# uino-1284p.net
KiCad netlist of a schematic drawn in EAGLE
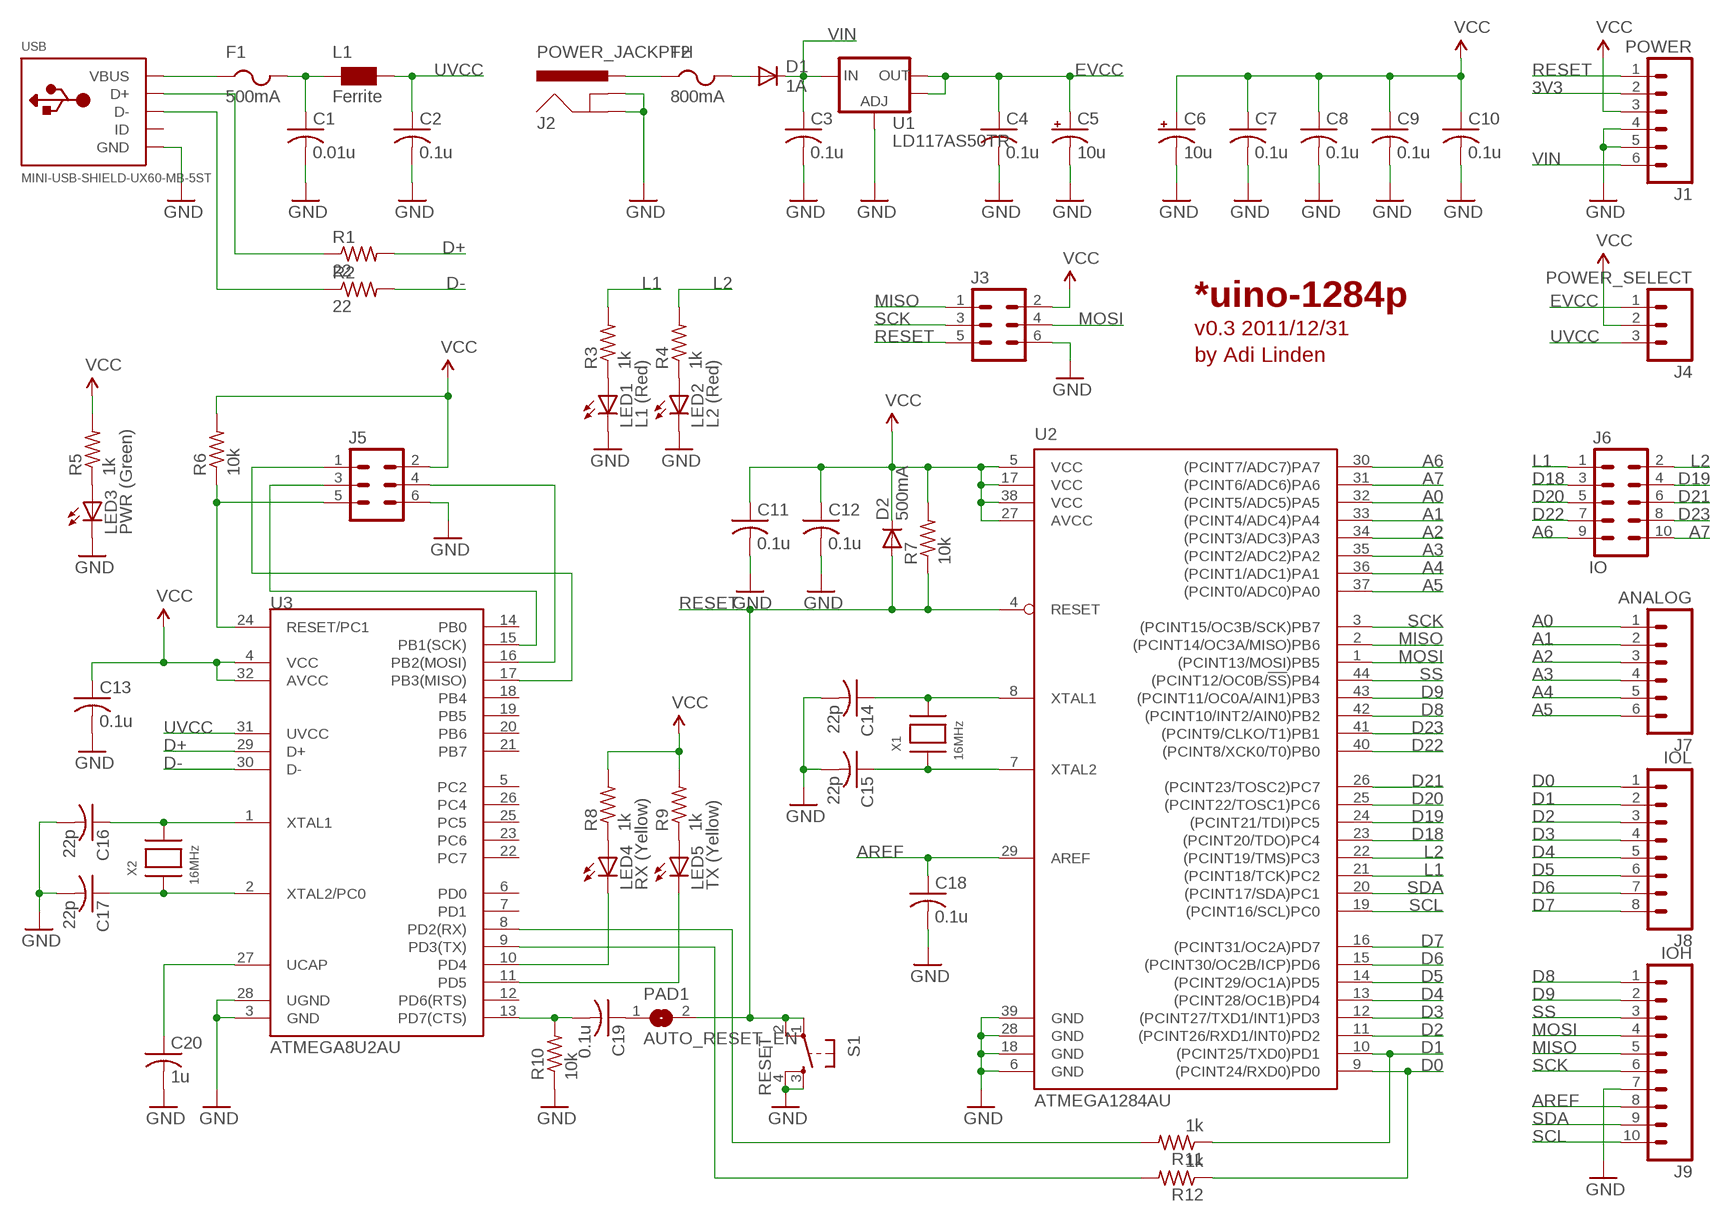
[diagram p0: schematic, sheet 1]

(export (version "E")
  (design (tool "Eeschema 10.0.6"))
  (components
    (comp (ref "C1")
      (value "0.01u")
      (footprint "eagle-import:C0805")
      (libsource (lib "eagle-import") (part "C-USC0805"))
    )
    (comp (ref "C2")
      (value "0.1u")
      (footprint "eagle-import:C0805")
      (libsource (lib "eagle-import") (part "C-USC0805"))
    )
    (comp (ref "C3")
      (value "0.1u")
      (footprint "eagle-import:C0805")
      (libsource (lib "eagle-import") (part "C-USC0805"))
    )
    (comp (ref "C4")
      (value "0.1u")
      (footprint "eagle-import:C0805")
      (libsource (lib "eagle-import") (part "C-USC0805"))
    )
    (comp (ref "C5")
      (value "10u")
      (footprint "eagle-import:CT3216")
      (libsource (lib "eagle-import") (part "CPOL-USCT3216"))
    )
    (comp (ref "C6")
      (value "10u")
      (footprint "eagle-import:CT3216")
      (libsource (lib "eagle-import") (part "CPOL-USCT3216"))
    )
    (comp (ref "C7")
      (value "0.1u")
      (footprint "eagle-import:C0805")
      (libsource (lib "eagle-import") (part "C-USC0805"))
    )
    (comp (ref "C8")
      (value "0.1u")
      (footprint "eagle-import:C0805")
      (libsource (lib "eagle-import") (part "C-USC0805"))
    )
    (comp (ref "C9")
      (value "0.1u")
      (footprint "eagle-import:C0805")
      (libsource (lib "eagle-import") (part "C-USC0805"))
    )
    (comp (ref "C10")
      (value "0.1u")
      (footprint "eagle-import:C0805")
      (libsource (lib "eagle-import") (part "C-USC0805"))
    )
    (comp (ref "C11")
      (value "0.1u")
      (footprint "eagle-import:C0805")
      (libsource (lib "eagle-import") (part "C-USC0805"))
    )
    (comp (ref "C12")
      (value "0.1u")
      (footprint "eagle-import:C0805")
      (libsource (lib "eagle-import") (part "C-USC0805"))
    )
    (comp (ref "C13")
      (value "0.1u")
      (footprint "eagle-import:C0805")
      (libsource (lib "eagle-import") (part "C-USC0805"))
    )
    (comp (ref "C14")
      (value "22p")
      (footprint "eagle-import:C0805")
      (libsource (lib "eagle-import") (part "C-USC0805"))
    )
    (comp (ref "C15")
      (value "22p")
      (footprint "eagle-import:C0805")
      (libsource (lib "eagle-import") (part "C-USC0805"))
    )
    (comp (ref "C16")
      (value "22p")
      (footprint "eagle-import:C0805")
      (libsource (lib "eagle-import") (part "C-USC0805"))
    )
    (comp (ref "C17")
      (value "22p")
      (footprint "eagle-import:C0805")
      (libsource (lib "eagle-import") (part "C-USC0805"))
    )
    (comp (ref "C18")
      (value "0.1u")
      (footprint "eagle-import:C0805")
      (libsource (lib "eagle-import") (part "C-USC0805"))
    )
    (comp (ref "C19")
      (value "0.1u")
      (footprint "eagle-import:C0805")
      (libsource (lib "eagle-import") (part "C-USC0805"))
    )
    (comp (ref "C20")
      (value "1u")
      (footprint "eagle-import:C0805")
      (libsource (lib "eagle-import") (part "C-USC0805"))
    )
    (comp (ref "D1")
      (value "1A")
      (footprint "eagle-import:SOD123")
      (libsource (lib "eagle-import") (part "MBR0520LT"))
    )
    (comp (ref "D2")
      (value "500mA")
      (footprint "eagle-import:SOD123")
      (libsource (lib "eagle-import") (part "MBR0520LT"))
    )
    (comp (ref "F1")
      (value "500mA")
      (footprint "eagle-import:R0805")
      (libsource (lib "eagle-import") (part "PTCFUSE-0805"))
    )
    (comp (ref "F2")
      (value "800mA")
      (footprint "eagle-import:R0805")
      (libsource (lib "eagle-import") (part "PTCFUSE-0805"))
    )
    (comp (ref "J1")
      (value "POWER")
      (footprint "eagle-import:1X06")
      (libsource (lib "eagle-import") (part "M06SIP"))
    )
    (comp (ref "J2")
      (value "POWER_JACKPTH")
      (footprint "eagle-import:POWER_JACK_PTH")
      (libsource (lib "eagle-import") (part "POWER_JACKPTH"))
    )
    (comp (ref "J3")
      (value "M03X2")
      (footprint "eagle-import:2X03")
      (libsource (lib "eagle-import") (part "M03X2"))
    )
    (comp (ref "J4")
      (value "POWER_SELECT")
      (footprint "eagle-import:1X03")
      (libsource (lib "eagle-import") (part "M03PTH"))
    )
    (comp (ref "J5")
      (value "M03X2")
      (footprint "eagle-import:2X03")
      (libsource (lib "eagle-import") (part "M03X2"))
    )
    (comp (ref "J6")
      (value "IO")
      (footprint "eagle-import:2X05")
      (libsource (lib "eagle-import") (part "M05X2"))
    )
    (comp (ref "J7")
      (value "ANALOG")
      (footprint "eagle-import:1X06")
      (libsource (lib "eagle-import") (part "M06SIP"))
    )
    (comp (ref "J8")
      (value "IOL")
      (footprint "eagle-import:1X08")
      (libsource (lib "eagle-import") (part "M081X08"))
    )
    (comp (ref "J9")
      (value "IOH")
      (footprint "eagle-import:1X10")
      (libsource (lib "eagle-import") (part "M101X10"))
    )
    (comp (ref "L1")
      (value "Ferrite")
      (footprint "eagle-import:0805")
      (libsource (lib "eagle-import") (part "WE-CBF_0805"))
    )
    (comp (ref "LED1")
      (value "L1 (Red)")
      (footprint "eagle-import:CHIP-LED0805")
      (libsource (lib "eagle-import") (part "LEDCHIP-LED0805"))
    )
    (comp (ref "LED2")
      (value "L2 (Red)")
      (footprint "eagle-import:CHIP-LED0805")
      (libsource (lib "eagle-import") (part "LEDCHIP-LED0805"))
    )
    (comp (ref "LED3")
      (value "PWR (Green)")
      (footprint "eagle-import:CHIP-LED0805")
      (libsource (lib "eagle-import") (part "LEDCHIP-LED0805"))
    )
    (comp (ref "LED4")
      (value "RX (Yellow)")
      (footprint "eagle-import:CHIP-LED0805")
      (libsource (lib "eagle-import") (part "LEDCHIP-LED0805"))
    )
    (comp (ref "LED5")
      (value "TX (Yellow)")
      (footprint "eagle-import:CHIP-LED0805")
      (libsource (lib "eagle-import") (part "LEDCHIP-LED0805"))
    )
    (comp (ref "PAD1")
      (value "AUTO_RESET_EN")
      (footprint "eagle-import:SJ")
      (libsource (lib "eagle-import") (part "SJ"))
    )
    (comp (ref "R1")
      (value "22")
      (footprint "eagle-import:R0805")
      (libsource (lib "eagle-import") (part "R-US_R0805"))
    )
    (comp (ref "R2")
      (value "22")
      (footprint "eagle-import:R0805")
      (libsource (lib "eagle-import") (part "R-US_R0805"))
    )
    (comp (ref "R3")
      (value "1k")
      (footprint "eagle-import:R0805")
      (libsource (lib "eagle-import") (part "R-US_R0805"))
    )
    (comp (ref "R4")
      (value "1k")
      (footprint "eagle-import:R0805")
      (libsource (lib "eagle-import") (part "R-US_R0805"))
    )
    (comp (ref "R5")
      (value "1k")
      (footprint "eagle-import:R0805")
      (libsource (lib "eagle-import") (part "R-US_R0805"))
    )
    (comp (ref "R6")
      (value "10k")
      (footprint "eagle-import:R0805")
      (libsource (lib "eagle-import") (part "R-US_R0805"))
    )
    (comp (ref "R7")
      (value "10k")
      (footprint "eagle-import:R0805")
      (libsource (lib "eagle-import") (part "R-US_R0805"))
    )
    (comp (ref "R8")
      (value "1k")
      (footprint "eagle-import:R0805")
      (libsource (lib "eagle-import") (part "R-US_R0805"))
    )
    (comp (ref "R9")
      (value "1k")
      (footprint "eagle-import:R0805")
      (libsource (lib "eagle-import") (part "R-US_R0805"))
    )
    (comp (ref "R10")
      (value "10k")
      (footprint "eagle-import:R0805")
      (libsource (lib "eagle-import") (part "R-US_R0805"))
    )
    (comp (ref "R11")
      (value "1k")
      (footprint "eagle-import:R0805")
      (libsource (lib "eagle-import") (part "R-US_R0805"))
    )
    (comp (ref "R12")
      (value "1k")
      (footprint "eagle-import:R0805")
      (libsource (lib "eagle-import") (part "R-US_R0805"))
    )
    (comp (ref "S1")
      (value "RESET")
      (footprint "eagle-import:TACTILE_SWITCH_SMD")
      (libsource (lib "eagle-import") (part "TAC_SWITCHSMD"))
    )
    (comp (ref "U1")
      (value "LD117AS50TR")
      (footprint "eagle-import:SOT223")
      (libsource (lib "eagle-import") (part "V_REG_LM1117SOT223"))
    )
    (comp (ref "U2")
      (value "ATMEGA1284AU")
      (footprint "eagle-import:TQFP44")
      (fields (field (name "MPN") "ATMEGA644PV-10AU"))
      (libsource (lib "eagle-import") (part "ATMEGA1284P-AU"))
    )
    (comp (ref "U3")
      (value "ATMEGA8U2AU")
      (footprint "eagle-import:TQFP32-08")
      (libsource (lib "eagle-import") (part "ATMEGA8U2AU"))
    )
    (comp (ref "USB")
      (value "MINI-USB-SHIELD-UX60-MB-5ST")
      (footprint "eagle-import:USB-MINIB")
      (libsource (lib "eagle-import") (part "USBMINIB"))
    )
    (comp (ref "X1")
      (value "16MHz")
      (footprint "eagle-import:NX5032")
      (libsource (lib "eagle-import") (part "XTALNX5032"))
    )
    (comp (ref "X2")
      (value "16MHz")
      (footprint "eagle-import:NX5032")
      (libsource (lib "eagle-import") (part "XTALNX5032"))
    )
  )
  (nets
    (net (code "1") (name "/3V3") (class "Default")
      (node (ref "J1") (pin "2") (pinfunction "2_2") (pintype "passive"))
    )
    (net (code "2") (name "/A0") (class "Default")
      (node (ref "J7") (pin "1") (pinfunction "1_1") (pintype "passive"))
      (node (ref "U2") (pin "32") (pinfunction "(PCINT5/ADC5)PA5_32") (pintype "bidirectional"))
    )
    (net (code "3") (name "/A1") (class "Default")
      (node (ref "J7") (pin "2") (pinfunction "2_2") (pintype "passive"))
      (node (ref "U2") (pin "33") (pinfunction "(PCINT4/ADC4)PA4_33") (pintype "bidirectional"))
    )
    (net (code "4") (name "/A2") (class "Default")
      (node (ref "J7") (pin "3") (pinfunction "3_3") (pintype "passive"))
      (node (ref "U2") (pin "34") (pinfunction "(PCINT3/ADC3)PA3_34") (pintype "bidirectional"))
    )
    (net (code "5") (name "/A3") (class "Default")
      (node (ref "J7") (pin "4") (pinfunction "4_4") (pintype "passive"))
      (node (ref "U2") (pin "35") (pinfunction "(PCINT2/ADC2)PA2_35") (pintype "bidirectional"))
    )
    (net (code "6") (name "/A4") (class "Default")
      (node (ref "J7") (pin "5") (pinfunction "5_5") (pintype "passive"))
      (node (ref "U2") (pin "36") (pinfunction "(PCINT1/ADC1)PA1_36") (pintype "bidirectional"))
    )
    (net (code "7") (name "/A5") (class "Default")
      (node (ref "J7") (pin "6") (pinfunction "6_6") (pintype "passive"))
      (node (ref "U2") (pin "37") (pinfunction "(PCINT0/ADC0)PA0_37") (pintype "bidirectional"))
    )
    (net (code "8") (name "/A6") (class "Default")
      (node (ref "J6") (pin "9") (pinfunction "9_9") (pintype "passive"))
      (node (ref "U2") (pin "30") (pinfunction "(PCINT7/ADC7)PA7_30") (pintype "bidirectional"))
    )
    (net (code "9") (name "/A7") (class "Default")
      (node (ref "J6") (pin "10") (pinfunction "10_10") (pintype "passive"))
      (node (ref "U2") (pin "31") (pinfunction "(PCINT6/ADC6)PA6_31") (pintype "bidirectional"))
    )
    (net (code "10") (name "/AREF") (class "Default")
      (node (ref "C18") (pin "1") (pinfunction "1_1") (pintype "passive"))
      (node (ref "J9") (pin "8") (pinfunction "8_8") (pintype "passive"))
      (node (ref "U2") (pin "29") (pinfunction "AREF_29") (pintype "passive"))
    )
    (net (code "11") (name "/D+") (class "Default")
      (node (ref "R1") (pin "2") (pinfunction "2_2") (pintype "passive"))
      (node (ref "U3") (pin "29") (pinfunction "D+_29") (pintype "bidirectional"))
    )
    (net (code "12") (name "/D-") (class "Default")
      (node (ref "R2") (pin "2") (pinfunction "2_2") (pintype "passive"))
      (node (ref "U3") (pin "30") (pinfunction "D-_30") (pintype "bidirectional"))
    )
    (net (code "13") (name "/D0") (class "Default")
      (node (ref "J8") (pin "1") (pinfunction "1_1") (pintype "passive"))
      (node (ref "R12") (pin "1") (pinfunction "1_1") (pintype "passive"))
      (node (ref "U2") (pin "9") (pinfunction "(PCINT24/RXD0)PD0_9") (pintype "bidirectional"))
    )
    (net (code "14") (name "/D1") (class "Default")
      (node (ref "J8") (pin "2") (pinfunction "2_2") (pintype "passive"))
      (node (ref "R11") (pin "1") (pinfunction "1_1") (pintype "passive"))
      (node (ref "U2") (pin "10") (pinfunction "(PCINT25/TXD0)PD1_10") (pintype "bidirectional"))
    )
    (net (code "15") (name "/D2") (class "Default")
      (node (ref "J8") (pin "3") (pinfunction "3_3") (pintype "passive"))
      (node (ref "U2") (pin "11") (pinfunction "(PCINT26/RXD1/INT0)PD2_11") (pintype "bidirectional"))
    )
    (net (code "16") (name "/D3") (class "Default")
      (node (ref "J8") (pin "4") (pinfunction "4_4") (pintype "passive"))
      (node (ref "U2") (pin "12") (pinfunction "(PCINT27/TXD1/INT1)PD3_12") (pintype "bidirectional"))
    )
    (net (code "17") (name "/D4") (class "Default")
      (node (ref "J8") (pin "5") (pinfunction "5_5") (pintype "passive"))
      (node (ref "U2") (pin "13") (pinfunction "(PCINT28/OC1B)PD4_13") (pintype "bidirectional"))
    )
    (net (code "18") (name "/D5") (class "Default")
      (node (ref "J8") (pin "6") (pinfunction "6_6") (pintype "passive"))
      (node (ref "U2") (pin "14") (pinfunction "(PCINT29/OC1A)PD5_14") (pintype "bidirectional"))
    )
    (net (code "19") (name "/D6") (class "Default")
      (node (ref "J8") (pin "7") (pinfunction "7_7") (pintype "passive"))
      (node (ref "U2") (pin "15") (pinfunction "(PCINT30/OC2B/ICP)PD6_15") (pintype "bidirectional"))
    )
    (net (code "20") (name "/D7") (class "Default")
      (node (ref "J8") (pin "8") (pinfunction "8_8") (pintype "passive"))
      (node (ref "U2") (pin "16") (pinfunction "(PCINT31/OC2A)PD7_16") (pintype "bidirectional"))
    )
    (net (code "21") (name "/D8") (class "Default")
      (node (ref "J9") (pin "1") (pinfunction "1_1") (pintype "passive"))
      (node (ref "U2") (pin "42") (pinfunction "(PCINT10/INT2/AIN0)PB2_42") (pintype "bidirectional"))
    )
    (net (code "22") (name "/D9") (class "Default")
      (node (ref "J9") (pin "2") (pinfunction "2_2") (pintype "passive"))
      (node (ref "U2") (pin "43") (pinfunction "(PCINT11/OC0A/AIN1)PB3_43") (pintype "bidirectional"))
    )
    (net (code "23") (name "/D18") (class "Default")
      (node (ref "J6") (pin "3") (pinfunction "3_3") (pintype "passive"))
      (node (ref "U2") (pin "23") (pinfunction "(PCINT20/TDO)PC4_23") (pintype "output"))
    )
    (net (code "24") (name "/D19") (class "Default")
      (node (ref "J6") (pin "4") (pinfunction "4_4") (pintype "passive"))
      (node (ref "U2") (pin "24") (pinfunction "(PCINT21/TDI)PC5_24") (pintype "output"))
    )
    (net (code "25") (name "/D20") (class "Default")
      (node (ref "J6") (pin "5") (pinfunction "5_5") (pintype "passive"))
      (node (ref "U2") (pin "25") (pinfunction "(PCINT22/TOSC1)PC6_25") (pintype "output"))
    )
    (net (code "26") (name "/D21") (class "Default")
      (node (ref "J6") (pin "6") (pinfunction "6_6") (pintype "passive"))
      (node (ref "U2") (pin "26") (pinfunction "(PCINT23/TOSC2)PC7_26") (pintype "output"))
    )
    (net (code "27") (name "/D22") (class "Default")
      (node (ref "J6") (pin "7") (pinfunction "7_7") (pintype "passive"))
      (node (ref "U2") (pin "40") (pinfunction "(PCINT8/XCK0/T0)PB0_40") (pintype "bidirectional"))
    )
    (net (code "28") (name "/D23") (class "Default")
      (node (ref "J6") (pin "8") (pinfunction "8_8") (pintype "passive"))
      (node (ref "U2") (pin "41") (pinfunction "(PCINT9/CLKO/T1)PB1_41") (pintype "bidirectional"))
    )
    (net (code "29") (name "/EVCC") (class "Default")
      (node (ref "C4") (pin "1") (pinfunction "1_1") (pintype "passive"))
      (node (ref "C5") (pin "+") (pinfunction "+_+") (pintype "passive"))
      (node (ref "J4") (pin "1") (pinfunction "1_1") (pintype "passive"))
      (node (ref "U1") (pin "2") (pinfunction "OUT_2") (pintype "power_in"))
      (node (ref "U1") (pin "4") (pinfunction "OUT_4") (pintype "power_in"))
    )
    (net (code "30") (name "/L1") (class "Default")
      (node (ref "J6") (pin "1") (pinfunction "1_1") (pintype "passive"))
      (node (ref "R3") (pin "2") (pinfunction "2_2") (pintype "passive"))
      (node (ref "U2") (pin "21") (pinfunction "(PCINT18/TCK)PC2_21") (pintype "output"))
    )
    (net (code "31") (name "/L2") (class "Default")
      (node (ref "J6") (pin "2") (pinfunction "2_2") (pintype "passive"))
      (node (ref "R4") (pin "2") (pinfunction "2_2") (pintype "passive"))
      (node (ref "U2") (pin "22") (pinfunction "(PCINT19/TMS)PC3_22") (pintype "output"))
    )
    (net (code "32") (name "/MISO") (class "Default")
      (node (ref "J3") (pin "1") (pinfunction "1_1") (pintype "passive"))
      (node (ref "J9") (pin "5") (pinfunction "5_5") (pintype "passive"))
      (node (ref "U2") (pin "2") (pinfunction "(PCINT14/OC3A/MISO)PB6_2") (pintype "bidirectional"))
    )
    (net (code "33") (name "/MOSI") (class "Default")
      (node (ref "J3") (pin "4") (pinfunction "4_4") (pintype "passive"))
      (node (ref "J9") (pin "4") (pinfunction "4_4") (pintype "passive"))
      (node (ref "U2") (pin "1") (pinfunction "(PCINT13/MOSI)PB5_1") (pintype "bidirectional"))
    )
    (net (code "34") (name "/RESET") (class "Default")
      (node (ref "D2") (pin "A") (pinfunction "A_A") (pintype "passive"))
      (node (ref "J1") (pin "1") (pinfunction "1_1") (pintype "passive"))
      (node (ref "J3") (pin "5") (pinfunction "5_5") (pintype "passive"))
      (node (ref "PAD1") (pin "2") (pinfunction "2_2") (pintype "passive"))
      (node (ref "R7") (pin "1") (pinfunction "1_1") (pintype "passive"))
      (node (ref "S1") (pin "1") (pinfunction "1_1") (pintype "passive"))
      (node (ref "S1") (pin "2") (pinfunction "2_2") (pintype "passive"))
      (node (ref "U2") (pin "4") (pinfunction "RESET_4") (pintype "input"))
    )
    (net (code "35") (name "/SCK") (class "Default")
      (node (ref "J3") (pin "3") (pinfunction "3_3") (pintype "passive"))
      (node (ref "J9") (pin "6") (pinfunction "6_6") (pintype "passive"))
      (node (ref "U2") (pin "3") (pinfunction "(PCINT15/OC3B/SCK)PB7_3") (pintype "bidirectional"))
    )
    (net (code "36") (name "/SCL") (class "Default")
      (node (ref "J9") (pin "10") (pinfunction "10_10") (pintype "passive"))
      (node (ref "U2") (pin "19") (pinfunction "(PCINT16/SCL)PC0_19") (pintype "output"))
    )
    (net (code "37") (name "/SDA") (class "Default")
      (node (ref "J9") (pin "9") (pinfunction "9_9") (pintype "passive"))
      (node (ref "U2") (pin "20") (pinfunction "(PCINT17/SDA)PC1_20") (pintype "output"))
    )
    (net (code "38") (name "/SS") (class "Default")
      (node (ref "J9") (pin "3") (pinfunction "3_3") (pintype "passive"))
      (node (ref "U2") (pin "44") (pinfunction "(PCINT12/OC0B/~{SS})PB4_44") (pintype "bidirectional"))
    )
    (net (code "39") (name "/UVCC") (class "Default")
      (node (ref "C2") (pin "1") (pinfunction "1_1") (pintype "passive"))
      (node (ref "J4") (pin "3") (pinfunction "3_3") (pintype "passive"))
      (node (ref "L1") (pin "2") (pinfunction "2_2") (pintype "passive"))
      (node (ref "U3") (pin "31") (pinfunction "UVCC_31") (pintype "bidirectional"))
    )
    (net (code "40") (name "/VIN") (class "Default")
      (node (ref "C3") (pin "1") (pinfunction "1_1") (pintype "passive"))
      (node (ref "D1") (pin "C") (pinfunction "C_C") (pintype "passive"))
      (node (ref "J1") (pin "6") (pinfunction "6_6") (pintype "passive"))
      (node (ref "U1") (pin "3") (pinfunction "IN_3") (pintype "input"))
    )
    (net (code "41") (name "GND") (class "Default")
      (node (ref "C1") (pin "2") (pinfunction "2_2") (pintype "passive"))
      (node (ref "C10") (pin "2") (pinfunction "2_2") (pintype "passive"))
      (node (ref "C11") (pin "2") (pinfunction "2_2") (pintype "passive"))
      (node (ref "C12") (pin "2") (pinfunction "2_2") (pintype "passive"))
      (node (ref "C13") (pin "2") (pinfunction "2_2") (pintype "passive"))
      (node (ref "C14") (pin "2") (pinfunction "2_2") (pintype "passive"))
      (node (ref "C15") (pin "2") (pinfunction "2_2") (pintype "passive"))
      (node (ref "C16") (pin "2") (pinfunction "2_2") (pintype "passive"))
      (node (ref "C17") (pin "2") (pinfunction "2_2") (pintype "passive"))
      (node (ref "C18") (pin "2") (pinfunction "2_2") (pintype "passive"))
      (node (ref "C2") (pin "2") (pinfunction "2_2") (pintype "passive"))
      (node (ref "C20") (pin "2") (pinfunction "2_2") (pintype "passive"))
      (node (ref "C3") (pin "2") (pinfunction "2_2") (pintype "passive"))
      (node (ref "C4") (pin "2") (pinfunction "2_2") (pintype "passive"))
      (node (ref "C5") (pin "-") (pinfunction "-_-") (pintype "passive"))
      (node (ref "C6") (pin "-") (pinfunction "-_-") (pintype "passive"))
      (node (ref "C7") (pin "2") (pinfunction "2_2") (pintype "passive"))
      (node (ref "C8") (pin "2") (pinfunction "2_2") (pintype "passive"))
      (node (ref "C9") (pin "2") (pinfunction "2_2") (pintype "passive"))
      (node (ref "J1") (pin "4") (pinfunction "4_4") (pintype "passive"))
      (node (ref "J1") (pin "5") (pinfunction "5_5") (pintype "passive"))
      (node (ref "J2") (pin "GND") (pinfunction "GND_GND") (pintype "bidirectional"))
      (node (ref "J2") (pin "GNDBREAK") (pinfunction "GNDBREAK_GNDBREAK") (pintype "bidirectional"))
      (node (ref "J3") (pin "6") (pinfunction "6_6") (pintype "passive"))
      (node (ref "J5") (pin "6") (pinfunction "6_6") (pintype "passive"))
      (node (ref "J9") (pin "7") (pinfunction "7_7") (pintype "passive"))
      (node (ref "LED1") (pin "C") (pinfunction "C_C") (pintype "passive"))
      (node (ref "LED2") (pin "C") (pinfunction "C_C") (pintype "passive"))
      (node (ref "LED3") (pin "C") (pinfunction "C_C") (pintype "passive"))
      (node (ref "R10") (pin "1") (pinfunction "1_1") (pintype "passive"))
      (node (ref "S1") (pin "3") (pinfunction "3_3") (pintype "passive"))
      (node (ref "S1") (pin "4") (pinfunction "4_4") (pintype "passive"))
      (node (ref "U1") (pin "1") (pinfunction "ADJ_1") (pintype "input"))
      (node (ref "U2") (pin "18") (pinfunction "GND_18") (pintype "power_in"))
      (node (ref "U2") (pin "28") (pinfunction "GND_28") (pintype "power_in"))
      (node (ref "U2") (pin "39") (pinfunction "GND_39") (pintype "power_in"))
      (node (ref "U2") (pin "6") (pinfunction "GND_6") (pintype "power_in"))
      (node (ref "U3") (pin "28") (pinfunction "UGND_28") (pintype "bidirectional"))
      (node (ref "U3") (pin "3") (pinfunction "GND_3") (pintype "bidirectional"))
      (node (ref "USB") (pin "GND") (pinfunction "GND_GND") (pintype "power_in"))
    )
    (net (code "42") (name "Net-(C1-Pad1)") (class "Default")
      (node (ref "C1") (pin "1") (pinfunction "1_1") (pintype "passive"))
      (node (ref "F1") (pin "2") (pinfunction "2_2") (pintype "passive"))
      (node (ref "L1") (pin "1") (pinfunction "1_1") (pintype "passive"))
    )
    (net (code "43") (name "Net-(C19-Pad1)") (class "Default")
      (node (ref "C19") (pin "1") (pinfunction "1_1") (pintype "passive"))
      (node (ref "PAD1") (pin "1") (pinfunction "1_1") (pintype "passive"))
    )
    (net (code "44") (name "Net-(D1-PadA)") (class "Default")
      (node (ref "D1") (pin "A") (pinfunction "A_A") (pintype "passive"))
      (node (ref "F2") (pin "2") (pinfunction "2_2") (pintype "passive"))
    )
    (net (code "45") (name "Net-(F1-Pad1)") (class "Default")
      (node (ref "F1") (pin "1") (pinfunction "1_1") (pintype "passive"))
      (node (ref "USB") (pin "VBUS") (pinfunction "VBUS_VBUS") (pintype "power_in"))
    )
    (net (code "46") (name "Net-(F2-Pad1)") (class "Default")
      (node (ref "F2") (pin "1") (pinfunction "1_1") (pintype "passive"))
      (node (ref "J2") (pin "PWR") (pinfunction "PWR_PWR") (pintype "bidirectional"))
    )
    (net (code "47") (name "Net-(LED1-PadA)") (class "Default")
      (node (ref "LED1") (pin "A") (pinfunction "A_A") (pintype "passive"))
      (node (ref "R3") (pin "1") (pinfunction "1_1") (pintype "passive"))
    )
    (net (code "48") (name "Net-(LED2-PadA)") (class "Default")
      (node (ref "LED2") (pin "A") (pinfunction "A_A") (pintype "passive"))
      (node (ref "R4") (pin "1") (pinfunction "1_1") (pintype "passive"))
    )
    (net (code "49") (name "Net-(LED3-PadA)") (class "Default")
      (node (ref "LED3") (pin "A") (pinfunction "A_A") (pintype "passive"))
      (node (ref "R5") (pin "1") (pinfunction "1_1") (pintype "passive"))
    )
    (net (code "50") (name "Net-(LED4-PadA)") (class "Default")
      (node (ref "LED4") (pin "A") (pinfunction "A_A") (pintype "passive"))
      (node (ref "R8") (pin "1") (pinfunction "1_1") (pintype "passive"))
    )
    (net (code "51") (name "Net-(LED5-PadA)") (class "Default")
      (node (ref "LED5") (pin "A") (pinfunction "A_A") (pintype "passive"))
      (node (ref "R9") (pin "1") (pinfunction "1_1") (pintype "passive"))
    )
    (net (code "52") (name "Net-(R1-Pad1)") (class "Default")
      (node (ref "R1") (pin "1") (pinfunction "1_1") (pintype "passive"))
      (node (ref "USB") (pin "D+") (pinfunction "D+_D+") (pintype "bidirectional"))
    )
    (net (code "53") (name "Net-(R2-Pad1)") (class "Default")
      (node (ref "R2") (pin "1") (pinfunction "1_1") (pintype "passive"))
      (node (ref "USB") (pin "D-") (pinfunction "D-_D-") (pintype "bidirectional"))
    )
    (net (code "54") (name "Net-(U2-XTAL1)") (class "Default")
      (node (ref "C14") (pin "1") (pinfunction "1_1") (pintype "passive"))
      (node (ref "U2") (pin "8") (pinfunction "XTAL1_8") (pintype "bidirectional"))
      (node (ref "X1") (pin "P$2") (pinfunction "P$2_P$2") (pintype "bidirectional"))
    )
    (net (code "55") (name "Net-(U2-XTAL2)") (class "Default")
      (node (ref "C15") (pin "1") (pinfunction "1_1") (pintype "passive"))
      (node (ref "U2") (pin "7") (pinfunction "XTAL2_7") (pintype "bidirectional"))
      (node (ref "X1") (pin "P$1") (pinfunction "P$1_P$1") (pintype "bidirectional"))
    )
    (net (code "56") (name "Net-(U3-PB1(SCK))") (class "Default")
      (node (ref "J5") (pin "3") (pinfunction "3_3") (pintype "passive"))
      (node (ref "U3") (pin "15") (pinfunction "PB1(SCK)_15") (pintype "bidirectional"))
    )
    (net (code "57") (name "Net-(U3-PB2(MOSI))") (class "Default")
      (node (ref "J5") (pin "4") (pinfunction "4_4") (pintype "passive"))
      (node (ref "U3") (pin "16") (pinfunction "PB2(MOSI)_16") (pintype "bidirectional"))
    )
    (net (code "58") (name "Net-(U3-PB3(MISO))") (class "Default")
      (node (ref "J5") (pin "1") (pinfunction "1_1") (pintype "passive"))
      (node (ref "U3") (pin "17") (pinfunction "PB3(MISO)_17") (pintype "bidirectional"))
    )
    (net (code "59") (name "Net-(U3-PD2(RX))") (class "Default")
      (node (ref "R11") (pin "2") (pinfunction "2_2") (pintype "passive"))
      (node (ref "U3") (pin "8") (pinfunction "PD2(RX)_8") (pintype "bidirectional"))
    )
    (net (code "60") (name "Net-(U3-PD3(TX))") (class "Default")
      (node (ref "R12") (pin "2") (pinfunction "2_2") (pintype "passive"))
      (node (ref "U3") (pin "9") (pinfunction "PD3(TX)_9") (pintype "bidirectional"))
    )
    (net (code "61") (name "Net-(U3-PD4)") (class "Default")
      (node (ref "LED4") (pin "C") (pinfunction "C_C") (pintype "passive"))
      (node (ref "U3") (pin "10") (pinfunction "PD4_10") (pintype "bidirectional"))
    )
    (net (code "62") (name "Net-(U3-PD5)") (class "Default")
      (node (ref "LED5") (pin "C") (pinfunction "C_C") (pintype "passive"))
      (node (ref "U3") (pin "11") (pinfunction "PD5_11") (pintype "bidirectional"))
    )
    (net (code "63") (name "Net-(U3-PD7(CTS))") (class "Default")
      (node (ref "C19") (pin "2") (pinfunction "2_2") (pintype "passive"))
      (node (ref "R10") (pin "2") (pinfunction "2_2") (pintype "passive"))
      (node (ref "U3") (pin "13") (pinfunction "PD7(CTS)_13") (pintype "bidirectional"))
    )
    (net (code "64") (name "Net-(U3-RESET{slash}PC1)") (class "Default")
      (node (ref "J5") (pin "5") (pinfunction "5_5") (pintype "passive"))
      (node (ref "R6") (pin "1") (pinfunction "1_1") (pintype "passive"))
      (node (ref "U3") (pin "24") (pinfunction "RESET/PC1_24") (pintype "bidirectional"))
    )
    (net (code "65") (name "Net-(U3-UCAP)") (class "Default")
      (node (ref "C20") (pin "1") (pinfunction "1_1") (pintype "passive"))
      (node (ref "U3") (pin "27") (pinfunction "UCAP_27") (pintype "bidirectional"))
    )
    (net (code "66") (name "Net-(U3-XTAL1)") (class "Default")
      (node (ref "C16") (pin "1") (pinfunction "1_1") (pintype "passive"))
      (node (ref "U3") (pin "1") (pinfunction "XTAL1_1") (pintype "bidirectional"))
      (node (ref "X2") (pin "P$2") (pinfunction "P$2_P$2") (pintype "bidirectional"))
    )
    (net (code "67") (name "Net-(U3-XTAL2{slash}PC0)") (class "Default")
      (node (ref "C17") (pin "1") (pinfunction "1_1") (pintype "passive"))
      (node (ref "U3") (pin "2") (pinfunction "XTAL2/PC0_2") (pintype "bidirectional"))
      (node (ref "X2") (pin "P$1") (pinfunction "P$1_P$1") (pintype "bidirectional"))
    )
    (net (code "68") (name "VCC") (class "Default")
      (node (ref "C10") (pin "1") (pinfunction "1_1") (pintype "passive"))
      (node (ref "C11") (pin "1") (pinfunction "1_1") (pintype "passive"))
      (node (ref "C12") (pin "1") (pinfunction "1_1") (pintype "passive"))
      (node (ref "C13") (pin "1") (pinfunction "1_1") (pintype "passive"))
      (node (ref "C6") (pin "+") (pinfunction "+_+") (pintype "passive"))
      (node (ref "C7") (pin "1") (pinfunction "1_1") (pintype "passive"))
      (node (ref "C8") (pin "1") (pinfunction "1_1") (pintype "passive"))
      (node (ref "C9") (pin "1") (pinfunction "1_1") (pintype "passive"))
      (node (ref "D2") (pin "C") (pinfunction "C_C") (pintype "passive"))
      (node (ref "J1") (pin "3") (pinfunction "3_3") (pintype "passive"))
      (node (ref "J3") (pin "2") (pinfunction "2_2") (pintype "passive"))
      (node (ref "J4") (pin "2") (pinfunction "2_2") (pintype "passive"))
      (node (ref "J5") (pin "2") (pinfunction "2_2") (pintype "passive"))
      (node (ref "R5") (pin "2") (pinfunction "2_2") (pintype "passive"))
      (node (ref "R6") (pin "2") (pinfunction "2_2") (pintype "passive"))
      (node (ref "R7") (pin "2") (pinfunction "2_2") (pintype "passive"))
      (node (ref "R8") (pin "2") (pinfunction "2_2") (pintype "passive"))
      (node (ref "R9") (pin "2") (pinfunction "2_2") (pintype "passive"))
      (node (ref "U2") (pin "17") (pinfunction "VCC_17") (pintype "power_in"))
      (node (ref "U2") (pin "27") (pinfunction "AVCC_27") (pintype "power_in"))
      (node (ref "U2") (pin "38") (pinfunction "VCC_38") (pintype "power_in"))
      (node (ref "U2") (pin "5") (pinfunction "VCC_5") (pintype "power_in"))
      (node (ref "U3") (pin "32") (pinfunction "AVCC_32") (pintype "bidirectional"))
      (node (ref "U3") (pin "4") (pinfunction "VCC_4") (pintype "bidirectional"))
    )
    (net (code "69") (name "unconnected-(U3-PB0-Pad14)") (class "Default")
      (node (ref "U3") (pin "14") (pinfunction "PB0_14") (pintype "bidirectional"))
    )
    (net (code "70") (name "unconnected-(U3-PB4-Pad18)") (class "Default")
      (node (ref "U3") (pin "18") (pinfunction "PB4_18") (pintype "bidirectional"))
    )
    (net (code "71") (name "unconnected-(U3-PB5-Pad19)") (class "Default")
      (node (ref "U3") (pin "19") (pinfunction "PB5_19") (pintype "bidirectional"))
    )
    (net (code "72") (name "unconnected-(U3-PB6-Pad20)") (class "Default")
      (node (ref "U3") (pin "20") (pinfunction "PB6_20") (pintype "bidirectional"))
    )
    (net (code "73") (name "unconnected-(U3-PB7-Pad21)") (class "Default")
      (node (ref "U3") (pin "21") (pinfunction "PB7_21") (pintype "bidirectional"))
    )
    (net (code "74") (name "unconnected-(U3-PC2-Pad5)") (class "Default")
      (node (ref "U3") (pin "5") (pinfunction "PC2_5") (pintype "bidirectional"))
    )
    (net (code "75") (name "unconnected-(U3-PC4-Pad26)") (class "Default")
      (node (ref "U3") (pin "26") (pinfunction "PC4_26") (pintype "bidirectional"))
    )
    (net (code "76") (name "unconnected-(U3-PC5-Pad25)") (class "Default")
      (node (ref "U3") (pin "25") (pinfunction "PC5_25") (pintype "bidirectional"))
    )
    (net (code "77") (name "unconnected-(U3-PC6-Pad23)") (class "Default")
      (node (ref "U3") (pin "23") (pinfunction "PC6_23") (pintype "bidirectional"))
    )
    (net (code "78") (name "unconnected-(U3-PC7-Pad22)") (class "Default")
      (node (ref "U3") (pin "22") (pinfunction "PC7_22") (pintype "bidirectional"))
    )
    (net (code "79") (name "unconnected-(U3-PD0-Pad6)") (class "Default")
      (node (ref "U3") (pin "6") (pinfunction "PD0_6") (pintype "bidirectional"))
    )
    (net (code "80") (name "unconnected-(U3-PD1-Pad7)") (class "Default")
      (node (ref "U3") (pin "7") (pinfunction "PD1_7") (pintype "bidirectional"))
    )
    (net (code "81") (name "unconnected-(U3-PD6(RTS)-Pad12)") (class "Default")
      (node (ref "U3") (pin "12") (pinfunction "PD6(RTS)_12") (pintype "bidirectional"))
    )
    (net (code "82") (name "unconnected-(USB-PadID)") (class "Default")
      (node (ref "USB") (pin "ID") (pinfunction "ID_ID") (pintype "bidirectional"))
    )
  )
)
